# Sheet.net
KiCad netlist of a schematic drawn in Altium Designer
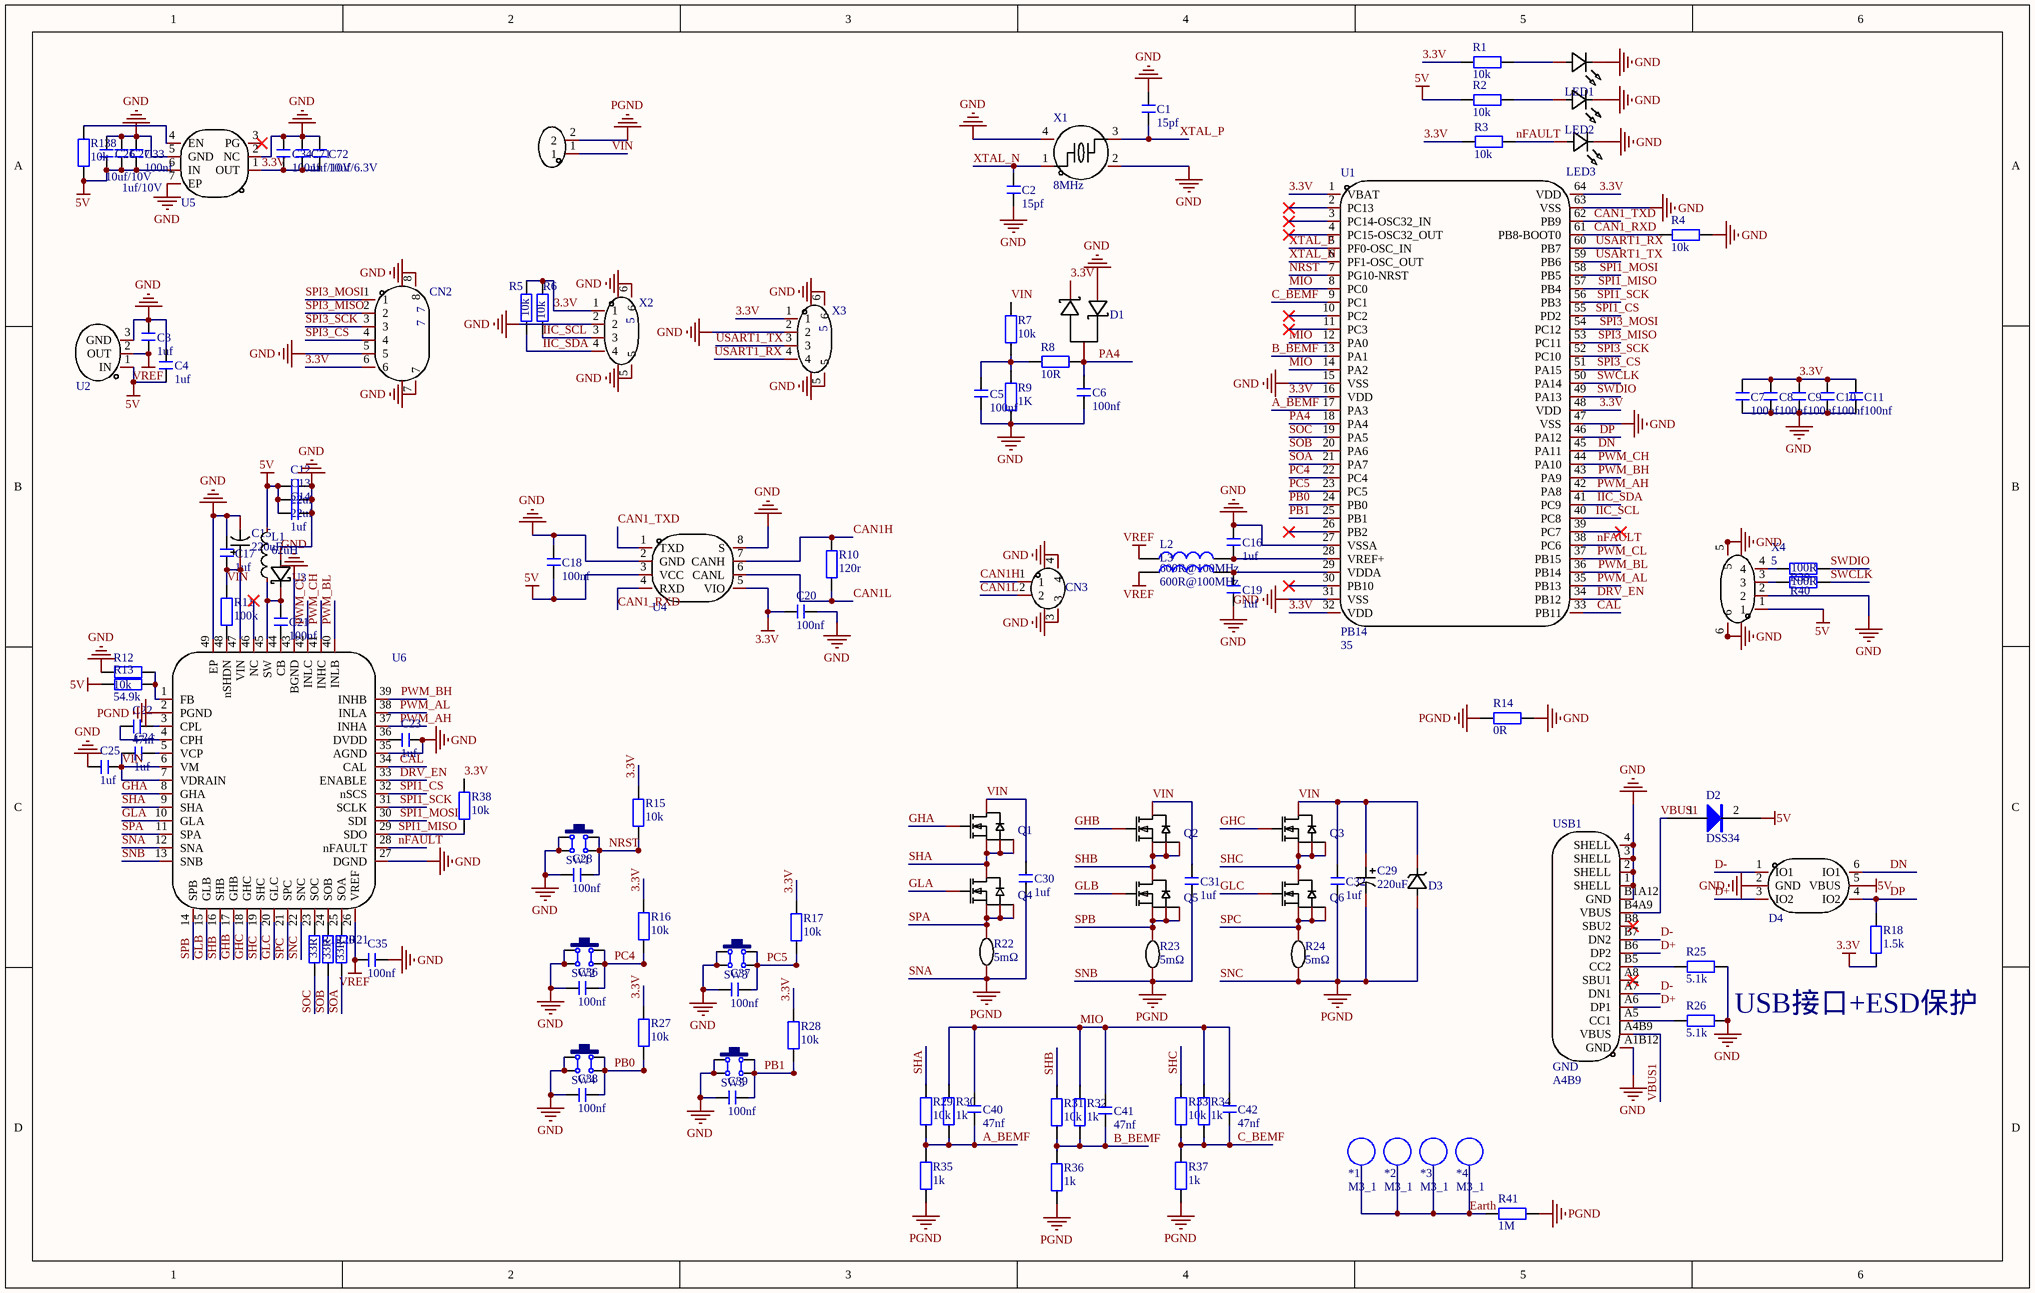
[diagram p0: Sheet.SchDoc]

(export (version "E")
  (design (tool "Eeschema 10.0.6"))
  (components
    (comp (ref "*1")
      (value "M3_1")
      (footprint "M3 125X250")
      (description "铜柱孔")
      (fields (field (name "版权归属") "源创客"))
      (libsource (lib "自用") (part "M3_1"))
    )
    (comp (ref "*2")
      (value "M3_1")
      (footprint "M3 125X250")
      (description "铜柱孔")
      (fields (field (name "版权归属") "源创客"))
      (libsource (lib "自用") (part "M3_1"))
    )
    (comp (ref "*3")
      (value "M3_1")
      (footprint "M3 125X250")
      (description "铜柱孔")
      (fields (field (name "版权归属") "源创客"))
      (libsource (lib "自用") (part "M3_1"))
    )
    (comp (ref "*4")
      (value "M3_1")
      (footprint "M3 125X250")
      (description "铜柱孔")
      (fields (field (name "版权归属") "源创客"))
      (libsource (lib "自用") (part "M3_1"))
    )
    (comp (ref "C1")
      (value "15pf")
      (footprint "C0402")
      (description "无极性电容")
      (fields (field (name "版权归属") "源创客"))
      (libsource (lib "自用") (part "C"))
    )
    (comp (ref "C2")
      (value "15pf")
      (footprint "C0402")
      (description "无极性电容")
      (fields (field (name "版权归属") "源创客"))
      (libsource (lib "自用") (part "C"))
    )
    (comp (ref "C3")
      (value "1uf")
      (footprint "C0402")
      (description "无极性电容")
      (fields (field (name "版权归属") "源创客"))
      (libsource (lib "自用") (part "C"))
    )
    (comp (ref "C4")
      (value "1uf")
      (footprint "C0402")
      (description "无极性电容")
      (fields (field (name "版权归属") "源创客"))
      (libsource (lib "自用") (part "C"))
    )
    (comp (ref "C5")
      (value "100nf")
      (footprint "C0402")
      (description "无极性电容")
      (fields (field (name "版权归属") "源创客"))
      (libsource (lib "自用") (part "C"))
    )
    (comp (ref "C6")
      (value "100nf")
      (footprint "C0402")
      (description "无极性电容")
      (fields (field (name "版权归属") "源创客"))
      (libsource (lib "自用") (part "C"))
    )
    (comp (ref "C7")
      (value "100nf")
      (footprint "C0402")
      (description "无极性电容")
      (fields (field (name "版权归属") "源创客"))
      (libsource (lib "自用") (part "C"))
    )
    (comp (ref "C8")
      (value "100nf")
      (footprint "C0402")
      (description "无极性电容")
      (fields (field (name "版权归属") "源创客"))
      (libsource (lib "自用") (part "C"))
    )
    (comp (ref "C9")
      (value "100nf")
      (footprint "C0402")
      (description "无极性电容")
      (fields (field (name "版权归属") "源创客"))
      (libsource (lib "自用") (part "C"))
    )
    (comp (ref "C10")
      (value "100nf")
      (footprint "C0402")
      (description "无极性电容")
      (fields (field (name "版权归属") "源创客"))
      (libsource (lib "自用") (part "C"))
    )
    (comp (ref "C11")
      (value "100nf")
      (footprint "C0402")
      (description "无极性电容")
      (fields (field (name "版权归属") "源创客"))
      (libsource (lib "自用") (part "C"))
    )
    (comp (ref "C12")
      (value "22uf")
      (footprint "C0402")
      (description "无极性电容")
      (fields (field (name "版权归属") "源创客"))
      (libsource (lib "自用") (part "C"))
    )
    (comp (ref "C13")
      (value "22uf")
      (footprint "C0402")
      (description "无极性电容")
      (fields (field (name "版权归属") "源创客"))
      (libsource (lib "自用") (part "C"))
    )
    (comp (ref "C14")
      (value "1uf")
      (footprint "C0402")
      (description "无极性电容")
      (fields (field (name "版权归属") "源创客"))
      (libsource (lib "自用") (part "C"))
    )
    (comp (ref "C15")
      (value "220uF")
      (footprint "CAP 2.5*5*11")
      (description "容值:220uF;精度:±20%;额定电压:50V;纹波电流:3.5A@100kHz;等效串联电阻(ESR):20mΩ@100kHz;类型:聚合物;")
      (fields (field (name "MANUFACTURER") "JIERR(捷而瑞)") (field (name "MANUFACTURER PART") "PA50V220M10x12"))
      (libsource (lib "自用") (part "电解电容M10*12"))
    )
    (comp (ref "C16")
      (value "1uf")
      (footprint "C0402")
      (description "无极性电容")
      (fields (field (name "版权归属") "源创客"))
      (libsource (lib "自用") (part "C"))
    )
    (comp (ref "C17")
      (value "1uf")
      (footprint "C1206")
      (description "无极性电容")
      (fields (field (name "版权归属") "源创客"))
      (libsource (lib "自用") (part "C"))
    )
    (comp (ref "C18")
      (value "100nf")
      (footprint "C0402")
      (description "无极性电容")
      (fields (field (name "版权归属") "源创客"))
      (libsource (lib "自用") (part "C"))
    )
    (comp (ref "C19")
      (value "1uf")
      (footprint "C0402")
      (description "无极性电容")
      (fields (field (name "版权归属") "源创客"))
      (libsource (lib "自用") (part "C"))
    )
    (comp (ref "C20")
      (value "100nf")
      (footprint "C0402")
      (description "无极性电容")
      (fields (field (name "版权归属") "源创客"))
      (libsource (lib "自用") (part "C"))
    )
    (comp (ref "C21")
      (value "100nf")
      (footprint "C0402")
      (description "无极性电容")
      (fields (field (name "版权归属") "源创客"))
      (libsource (lib "自用") (part "C"))
    )
    (comp (ref "C22")
      (value "47nf")
      (footprint "C0402")
      (description "无极性电容")
      (fields (field (name "版权归属") "源创客"))
      (libsource (lib "自用") (part "C"))
    )
    (comp (ref "C23")
      (value "1uf")
      (footprint "C0402")
      (description "无极性电容")
      (fields (field (name "版权归属") "源创客"))
      (libsource (lib "自用") (part "C"))
    )
    (comp (ref "C24")
      (value "1uf")
      (footprint "C0402")
      (description "无极性电容")
      (fields (field (name "版权归属") "源创客"))
      (libsource (lib "自用") (part "C"))
    )
    (comp (ref "C25")
      (value "1uf")
      (footprint "C0402")
      (description "无极性电容")
      (fields (field (name "版权归属") "源创客"))
      (libsource (lib "自用") (part "C"))
    )
    (comp (ref "C26")
      (value "10uf/10V")
      (footprint "C0603")
      (description "无极性电容")
      (fields (field (name "版权归属") "源创客"))
      (libsource (lib "自用") (part "C"))
    )
    (comp (ref "C27")
      (value "1uf/10V")
      (footprint "C0402")
      (description "无极性电容")
      (fields (field (name "版权归属") "源创客"))
      (libsource (lib "自用") (part "C"))
    )
    (comp (ref "C28")
      (value "100nf")
      (footprint "C0402")
      (description "无极性电容")
      (fields (field (name "版权归属") "源创客"))
      (libsource (lib "自用") (part "C"))
    )
    (comp (ref "C29")
      (value "220uF")
      (footprint "CAP-TH_BD10.0-P5.00-D0.6-FD_2")
      (description "容值:220uF;精度:±20%;额定电压:50V;纹波电流:3.5A@100kHz;等效串联电阻(ESR):20mΩ@100kHz;类型:聚合物;")
      (fields (field (name "MANUFACTURER") "JIERR(捷而瑞)") (field (name "MANUFACTURER PART") "PA50V220M10x12"))
      (libsource (lib "自用") (part "电解电容M10*12"))
    )
    (comp (ref "C30")
      (value "1uf")
      (footprint "C1206")
      (description "无极性电容")
      (fields (field (name "版权归属") "源创客"))
      (libsource (lib "自用") (part "C"))
    )
    (comp (ref "C31")
      (value "1uf")
      (footprint "C1206")
      (description "无极性电容")
      (fields (field (name "版权归属") "源创客"))
      (libsource (lib "自用") (part "C"))
    )
    (comp (ref "C32")
      (value "1uf")
      (footprint "C1206")
      (description "无极性电容")
      (fields (field (name "版权归属") "源创客"))
      (libsource (lib "自用") (part "C"))
    )
    (comp (ref "C33")
      (value "100nf")
      (footprint "C0402")
      (description "无极性电容")
      (fields (field (name "版权归属") "源创客"))
      (libsource (lib "自用") (part "C"))
    )
    (comp (ref "C34")
      (value "100nf")
      (footprint "C0402")
      (description "无极性电容")
      (fields (field (name "版权归属") "源创客"))
      (libsource (lib "自用") (part "C"))
    )
    (comp (ref "C35")
      (value "100nf")
      (footprint "C0402")
      (description "无极性电容")
      (fields (field (name "版权归属") "源创客"))
      (libsource (lib "自用") (part "C"))
    )
    (comp (ref "C36")
      (value "100nf")
      (footprint "C0402")
      (description "无极性电容")
      (fields (field (name "版权归属") "源创客"))
      (libsource (lib "自用") (part "C"))
    )
    (comp (ref "C37")
      (value "100nf")
      (footprint "C0402")
      (description "无极性电容")
      (fields (field (name "版权归属") "源创客"))
      (libsource (lib "自用") (part "C"))
    )
    (comp (ref "C38")
      (value "100nf")
      (footprint "C0402")
      (description "无极性电容")
      (fields (field (name "版权归属") "源创客"))
      (libsource (lib "自用") (part "C"))
    )
    (comp (ref "C39")
      (value "100nf")
      (footprint "C0402")
      (description "无极性电容")
      (fields (field (name "版权归属") "源创客"))
      (libsource (lib "自用") (part "C"))
    )
    (comp (ref "C40")
      (value "47nf")
      (footprint "C0402")
      (description "无极性电容")
      (fields (field (name "版权归属") "源创客"))
      (libsource (lib "自用") (part "C"))
    )
    (comp (ref "C41")
      (value "47nf")
      (footprint "C0402")
      (description "无极性电容")
      (fields (field (name "版权归属") "源创客"))
      (libsource (lib "自用") (part "C"))
    )
    (comp (ref "C42")
      (value "47nf")
      (footprint "C0402")
      (description "无极性电容")
      (fields (field (name "版权归属") "源创客"))
      (libsource (lib "自用") (part "C"))
    )
    (comp (ref "C71")
      (value "1uf/10V")
      (footprint "C0402")
      (description "无极性电容")
      (fields (field (name "版权归属") "源创客"))
      (libsource (lib "自用") (part "C"))
    )
    (comp (ref "C72")
      (value "10uf/6.3V")
      (footprint "C0603")
      (description "无极性电容")
      (fields (field (name "版权归属") "源创客"))
      (libsource (lib "自用") (part "C"))
    )
    (comp (ref "CN1")
      (value "XT30U-M")
      (footprint "CONN-TH_XT30U-M")
      (fields (field (name "MANUFACTURER") "AMASS(艾迈斯)"))
      (libsource (lib "自用") (part "XT30U-M"))
    )
    (comp (ref "CN2")
      (value "A1257WR-S-6P")
      (footprint "CONN-SMD_A1257WR-S-6P")
      (description "插针结构:1x6P;间距:1.25mm;安装方式:-;行距:-;总PIN数:6P;排数:1;每排PIN数:6;参考系列:GH;触头材质:黄铜;")
      (fields
        (field (name "MANUFACTURER") "CJT(长江连接器)")
        (field (name "NAME") "7")
        (field (name "NUMBER") "7")
      )
      (libsource (lib "自用") (part "GH1.25-6P"))
    )
    (comp (ref "CN3")
      (value "GH125-S02DCA-00")
      (footprint "GH1.25-2P-卧贴")
      (fields (field (name "MANUFACTURER") "JS(钜硕电子)"))
      (libsource (lib "自用") (part "GH125-2p"))
    )
    (comp (ref "D1")
      (value "LBAT54SLT1G")
      (footprint "SOT-23_L2.9-W1.3-P1.90-LS2.4-BR")
      (description "正向压降(Vf):400mV;直流反向耐压(Vr):30V;整流电流:200mA;")
      (fields (field (name "MANUFACTURER") "LRC(乐山无线电)"))
      (libsource (lib "自用") (part "LBAT54SLT1G"))
    )
    (comp (ref "D2")
      (value "DSS34")
      (footprint "SOD-123")
      (description "Diode 1N series")
      (libsource (lib "自用") (part "二极管"))
    )
    (comp (ref "D3")
      (value "SMBJ60A_C49066953")
      (footprint "SMB_L4.5-W3.7-LS5.4-RD")
      (description "极性:单向;反向截止电压(Vrwm):60V;钳位电压:96.8V;峰值脉冲电流(Ipp):6.2A;峰值脉冲功率(Ppp):600W;击穿电压:73.7V;")
      (fields (field (name "MANUFACTURER") "R+O(宏嘉诚)") (field (name "MANUFACTURER PART") "SMBJ60A"))
      (libsource (lib "自用") (part "SMBJ60A_C49066953"))
    )
    (comp (ref "D4")
      (value "USBLC6-2SC6_C2827654")
      (footprint "SOT-23-6_L2.9-W1.6-P0.95-LS2.8-BL")
      (description "极性:-;反向截止电压(Vrwm):-;最大钳位电压:-;峰值脉冲电流(Ipp)@10/1000us:-;峰值脉冲功率(Ppp)@10/1000us:-;击穿电压:-;")
      (fields
        (field (name "MANUFACTURER") "TECH PUBLIC(台舟)")
        (field (name "MANUFACTURER PART") "USBLC6-2SC6")
      )
      (libsource (lib "自用") (part "USBLC6-2SC6_C2827654"))
    )
    (comp (ref "L1")
      (value "62uH")
      (footprint "IND-SMD_L4.0-W4.0_FNR40XXS")
      (description "电感值:62uH;精度:±20%;额定电流:520mA;饱和电流(Isat):710mA;类型:磁胶屏蔽电感;")
      (fields (field (name "MANUFACTURER") "cjiang(长江微电)") (field (name "MANUFACTURER PART") "FNR4020S620MT"))
      (libsource (lib "自用") (part "FNR4020S620MT"))
    )
    (comp (ref "L2")
      (value "600R@100MHz")
      (footprint "L0603")
      (description "电感")
      (fields (field (name "版权归属") "源创客"))
      (libsource (lib "自用") (part "L_1"))
    )
    (comp (ref "L3")
      (value "600R@100MHz")
      (footprint "L0603")
      (description "电感")
      (fields (field (name "版权归属") "源创客"))
      (libsource (lib "自用") (part "L_1"))
    )
    (comp (ref "LED1")
      (value "XL-1005SURC")
      (footprint "LED0402-R-RD_RED")
      (description "发光颜色:红色;功率:55mW;正向电流:25mA;主波长:620nm;透镜颜色:无色透明透镜;色温:6000K~7000K;发光角度:120°;载带方式:正贴;工作温度:-30~+85;")
      (fields (field (name "MANUFACTURER") "XINGLIGHT(成兴光)"))
      (libsource (lib "自用") (part "LED_1"))
    )
    (comp (ref "LED2")
      (value "XL-1005SURC")
      (footprint "LED0402-R-RD_RED")
      (description "发光颜色:红色;功率:55mW;正向电流:25mA;主波长:620nm;透镜颜色:无色透明透镜;色温:6000K~7000K;发光角度:120°;载带方式:正贴;工作温度:-30~+85;")
      (fields (field (name "MANUFACTURER") "XINGLIGHT(成兴光)"))
      (libsource (lib "自用") (part "LED_1"))
    )
    (comp (ref "LED3")
      (value "XL-1005SURC")
      (footprint "LED0402-R-RD_RED")
      (description "发光颜色:红色;功率:55mW;正向电流:25mA;主波长:620nm;透镜颜色:无色透明透镜;色温:6000K~7000K;发光角度:120°;载带方式:正贴;工作温度:-30~+85;")
      (fields (field (name "MANUFACTURER") "XINGLIGHT(成兴光)"))
      (libsource (lib "自用") (part "LED_1"))
    )
    (comp (ref "Q1")
      (value "NCEP0160AG")
      (footprint "DFN-5_L4.9-W5.9-P1.27-LS6.2-BL")
      (fields (field (name "MANUFACTURER") "NCE(无锡新洁能)"))
      (libsource (lib "自用") (part "NCEP0160AG"))
    )
    (comp (ref "Q2")
      (value "NCEP0160AG")
      (footprint "DFN-5_L4.9-W5.9-P1.27-LS6.2-BL")
      (fields (field (name "MANUFACTURER") "NCE(无锡新洁能)"))
      (libsource (lib "自用") (part "NCEP0160AG"))
    )
    (comp (ref "Q3")
      (value "NCEP0160AG")
      (footprint "DFN-5_L4.9-W5.9-P1.27-LS6.2-BL")
      (fields (field (name "MANUFACTURER") "NCE(无锡新洁能)"))
      (libsource (lib "自用") (part "NCEP0160AG"))
    )
    (comp (ref "Q4")
      (value "NCEP0160AG")
      (footprint "DFN-5_L4.9-W5.9-P1.27-LS6.2-BL")
      (fields (field (name "MANUFACTURER") "NCE(无锡新洁能)"))
      (libsource (lib "自用") (part "NCEP0160AG"))
    )
    (comp (ref "Q5")
      (value "NCEP0160AG")
      (footprint "DFN-5_L4.9-W5.9-P1.27-LS6.2-BL")
      (fields (field (name "MANUFACTURER") "NCE(无锡新洁能)"))
      (libsource (lib "自用") (part "NCEP0160AG"))
    )
    (comp (ref "Q6")
      (value "NCEP0160AG")
      (footprint "DFN-5_L4.9-W5.9-P1.27-LS6.2-BL")
      (fields (field (name "MANUFACTURER") "NCE(无锡新洁能)"))
      (libsource (lib "自用") (part "NCEP0160AG"))
    )
    (comp (ref "R1")
      (value "10k")
      (footprint "R0402")
      (description "电阻")
      (fields (field (name "版权归属") "源创客"))
      (libsource (lib "自用") (part "R"))
    )
    (comp (ref "R2")
      (value "10k")
      (footprint "R0402")
      (description "电阻")
      (fields (field (name "版权归属") "源创客"))
      (libsource (lib "自用") (part "R"))
    )
    (comp (ref "R3")
      (value "10k")
      (footprint "R0402")
      (description "电阻")
      (fields (field (name "版权归属") "源创客"))
      (libsource (lib "自用") (part "R"))
    )
    (comp (ref "R4")
      (value "10k")
      (footprint "R0402")
      (description "电阻")
      (fields (field (name "版权归属") "源创客"))
      (libsource (lib "自用") (part "R"))
    )
    (comp (ref "R5")
      (value "10k")
      (footprint "R0402")
      (description "电阻")
      (fields (field (name "版权归属") "源创客"))
      (libsource (lib "自用") (part "R"))
    )
    (comp (ref "R6")
      (value "10k")
      (footprint "R0402")
      (description "电阻")
      (fields (field (name "版权归属") "源创客"))
      (libsource (lib "自用") (part "R"))
    )
    (comp (ref "R7")
      (value "10k")
      (footprint "R0402")
      (description "电阻")
      (fields (field (name "版权归属") "源创客"))
      (libsource (lib "自用") (part "R"))
    )
    (comp (ref "R8")
      (value "10R")
      (footprint "R0402")
      (description "电阻")
      (fields (field (name "版权归属") "源创客"))
      (libsource (lib "自用") (part "R"))
    )
    (comp (ref "R9")
      (value "1K")
      (footprint "R0402")
      (description "电阻")
      (fields (field (name "版权归属") "源创客"))
      (libsource (lib "自用") (part "R"))
    )
    (comp (ref "R10")
      (value "120r")
      (footprint "R0402")
      (description "电阻")
      (fields (field (name "版权归属") "源创客"))
      (libsource (lib "自用") (part "R"))
    )
    (comp (ref "R11")
      (value "100k")
      (footprint "R0402")
      (description "电阻")
      (fields (field (name "版权归属") "源创客"))
      (libsource (lib "自用") (part "R"))
    )
    (comp (ref "R12")
      (value "10k")
      (footprint "R0402")
      (description "电阻")
      (fields (field (name "版权归属") "源创客"))
      (libsource (lib "自用") (part "R"))
    )
    (comp (ref "R13")
      (value "54.9k")
      (footprint "R0402")
      (description "电阻")
      (fields (field (name "版权归属") "源创客"))
      (libsource (lib "自用") (part "R"))
    )
    (comp (ref "R14")
      (value "0R")
      (footprint "0805R")
      (description "电阻")
      (fields (field (name "版权归属") "源创客"))
      (libsource (lib "自用") (part "R"))
    )
    (comp (ref "R15")
      (value "10k")
      (footprint "R0402")
      (description "电阻")
      (fields (field (name "版权归属") "源创客"))
      (libsource (lib "自用") (part "R"))
    )
    (comp (ref "R16")
      (value "10k")
      (footprint "R0402")
      (description "电阻")
      (fields (field (name "版权归属") "源创客"))
      (libsource (lib "自用") (part "R"))
    )
    (comp (ref "R17")
      (value "10k")
      (footprint "R0402")
      (description "电阻")
      (fields (field (name "版权归属") "源创客"))
      (libsource (lib "自用") (part "R"))
    )
    (comp (ref "R18")
      (value "1.5k")
      (footprint "R0402")
      (description "电阻")
      (fields (field (name "版权归属") "源创客"))
      (libsource (lib "自用") (part "R"))
    )
    (comp (ref "R19")
      (value "33R")
      (footprint "R0402")
      (description "电阻")
      (fields (field (name "版权归属") "源创客"))
      (libsource (lib "自用") (part "R"))
    )
    (comp (ref "R20")
      (value "33R")
      (footprint "R0402")
      (description "电阻")
      (fields (field (name "版权归属") "源创客"))
      (libsource (lib "自用") (part "R"))
    )
    (comp (ref "R21")
      (value "33R")
      (footprint "R0402")
      (description "电阻")
      (fields (field (name "版权归属") "源创客"))
      (libsource (lib "自用") (part "R"))
    )
    (comp (ref "R22")
      (value "5mΩ")
      (footprint "R2512")
      (description "电阻类型:采样电阻;阻值:5mΩ;精度:±1%;功率:2W;安装方式:贴片;")
      (fields
        (field (name "MANUFACTURER") "Milliohm(毫欧)")
        (field (name "MANUFACTURER PART") "HoYLR2512-2W-5mR-1%")
      )
      (libsource (lib "自用") (part "HoYLR2512-2W-5mR-1%"))
    )
    (comp (ref "R23")
      (value "5mΩ")
      (footprint "R2512")
      (description "电阻类型:采样电阻;阻值:5mΩ;精度:±1%;功率:2W;安装方式:贴片;")
      (fields
        (field (name "MANUFACTURER") "Milliohm(毫欧)")
        (field (name "MANUFACTURER PART") "HoYLR2512-2W-5mR-1%")
      )
      (libsource (lib "自用") (part "HoYLR2512-2W-5mR-1%"))
    )
    (comp (ref "R24")
      (value "5mΩ")
      (footprint "R2512")
      (description "电阻类型:采样电阻;阻值:5mΩ;精度:±1%;功率:2W;安装方式:贴片;")
      (fields
        (field (name "MANUFACTURER") "Milliohm(毫欧)")
        (field (name "MANUFACTURER PART") "HoYLR2512-2W-5mR-1%")
      )
      (libsource (lib "自用") (part "HoYLR2512-2W-5mR-1%"))
    )
    (comp (ref "R25")
      (value "5.1k")
      (footprint "R0402")
      (description "电阻")
      (fields (field (name "版权归属") "源创客"))
      (libsource (lib "自用") (part "R"))
    )
    (comp (ref "R26")
      (value "5.1k")
      (footprint "R0402")
      (description "电阻")
      (fields (field (name "版权归属") "源创客"))
      (libsource (lib "自用") (part "R"))
    )
    (comp (ref "R27")
      (value "10k")
      (footprint "R0402")
      (description "电阻")
      (fields (field (name "版权归属") "源创客"))
      (libsource (lib "自用") (part "R"))
    )
    (comp (ref "R28")
      (value "10k")
      (footprint "R0402")
      (description "电阻")
      (fields (field (name "版权归属") "源创客"))
      (libsource (lib "自用") (part "R"))
    )
    (comp (ref "R29")
      (value "10k")
      (footprint "R0402")
      (description "电阻")
      (fields (field (name "版权归属") "源创客"))
      (libsource (lib "自用") (part "R"))
    )
    (comp (ref "R30")
      (value "1k")
      (footprint "R0402")
      (description "电阻")
      (fields (field (name "版权归属") "源创客"))
      (libsource (lib "自用") (part "R"))
    )
    (comp (ref "R31")
      (value "10k")
      (footprint "R0402")
      (description "电阻")
      (fields (field (name "版权归属") "源创客"))
      (libsource (lib "自用") (part "R"))
    )
    (comp (ref "R32")
      (value "1k")
      (footprint "R0402")
      (description "电阻")
      (fields (field (name "版权归属") "源创客"))
      (libsource (lib "自用") (part "R"))
    )
    (comp (ref "R33")
      (value "10k")
      (footprint "R0402")
      (description "电阻")
      (fields (field (name "版权归属") "源创客"))
      (libsource (lib "自用") (part "R"))
    )
    (comp (ref "R34")
      (value "1k")
      (footprint "R0402")
      (description "电阻")
      (fields (field (name "版权归属") "源创客"))
      (libsource (lib "自用") (part "R"))
    )
    (comp (ref "R35")
      (value "1k")
      (footprint "R0402")
      (description "电阻")
      (fields (field (name "版权归属") "源创客"))
      (libsource (lib "自用") (part "R"))
    )
    (comp (ref "R36")
      (value "1k")
      (footprint "R0402")
      (description "电阻")
      (fields (field (name "版权归属") "源创客"))
      (libsource (lib "自用") (part "R"))
    )
    (comp (ref "R37")
      (value "1k")
      (footprint "R0402")
      (description "电阻")
      (fields (field (name "版权归属") "源创客"))
      (libsource (lib "自用") (part "R"))
    )
    (comp (ref "R38")
      (value "10k")
      (footprint "R0402")
      (description "电阻")
      (fields (field (name "版权归属") "源创客"))
      (libsource (lib "自用") (part "R"))
    )
    (comp (ref "R39")
      (value "100R")
      (footprint "R0402")
      (description "电阻")
      (fields (field (name "版权归属") "源创客"))
      (libsource (lib "自用") (part "R"))
    )
    (comp (ref "R40")
      (value "100R")
      (footprint "R0402")
      (description "电阻")
      (fields (field (name "版权归属") "源创客"))
      (libsource (lib "自用") (part "R"))
    )
    (comp (ref "R41")
      (value "1M")
      (footprint "0805R")
      (description "电阻")
      (fields (field (name "版权归属") "源创客"))
      (libsource (lib "自用") (part "R"))
    )
    (comp (ref "R138")
      (value "10k")
      (footprint "R0402")
      (description "电阻")
      (fields (field (name "版权归属") "源创客"))
      (libsource (lib "自用") (part "R"))
    )
    (comp (ref "SW1")
      (value "smd-4*4*1.5")
      (footprint "TSW SMD-4*4*1.5")
      (description "轻触开关")
      (fields (field (name "版权归属") "源创客"))
      (libsource (lib "自用") (part "TSW DIP-6x6"))
    )
    (comp (ref "SW2")
      (value "smd-4*4*1.5")
      (footprint "TSW SMD-4*4*1.5")
      (description "轻触开关")
      (fields (field (name "版权归属") "源创客"))
      (libsource (lib "自用") (part "TSW DIP-6x6"))
    )
    (comp (ref "SW3")
      (value "smd-4*4*1.5")
      (footprint "TSW SMD-4*4*1.5")
      (description "轻触开关")
      (fields (field (name "版权归属") "源创客"))
      (libsource (lib "自用") (part "TSW DIP-6x6"))
    )
    (comp (ref "SW4")
      (value "smd-4*4*1.5")
      (footprint "TSW SMD-4*4*1.5")
      (description "轻触开关")
      (fields (field (name "版权归属") "源创客"))
      (libsource (lib "自用") (part "TSW DIP-6x6"))
    )
    (comp (ref "SW5")
      (value "smd-4*4*1.5")
      (footprint "TSW SMD-4*4*1.5")
      (description "轻触开关")
      (fields (field (name "版权归属") "源创客"))
      (libsource (lib "自用") (part "TSW DIP-6x6"))
    )
    (comp (ref "U1")
      (value "STM32G474RET6")
      (footprint "LQFP-64_L10.0-W10.0-P0.50-LS12.0-BL")
      (description "CPU内核:ARM-M4;CPU最大主频:170MHz;应用领域:-;")
      (fields
        (field (name "MANUFACTURER") "ST(意法半导体)")
        (field (name "NAME") "PB14")
        (field (name "NUMBER") "35")
      )
      (libsource (lib "自用") (part "STM32G474RET6"))
    )
    (comp (ref "U2")
      (value "REF3033AIDBZR")
      (footprint "SOT-23-3_L3.0-W1.7-P0.95-LS2.9-BR")
      (description "输出类型:固定;工作电压:3.35V~5.5V;输出电压:3.3V;输出电流:25mA;精度:±0.2%;")
      (fields (field (name "MANUFACTURER") "TI(德州仪器)") (field (name "TOLERANCE") "±0.2%"))
      (libsource (lib "自用") (part "REF3033AIDBZR"))
    )
    (comp (ref "U3")
      (value "DSK16_C22466351")
      (footprint "SOD-123FL_L2.8-W1.9-LS3.7-RD")
      (description "二极管配置:独立式;正向压降(Vf):700mV@1A;直流反向耐压(Vr):60V;整流电流:1A;")
      (fields (field (name "MANUFACTURER") "R+O(宏嘉诚)") (field (name "MANUFACTURER PART") "DSK16"))
      (libsource (lib "自用") (part "DSK16_C22466351"))
    )
    (comp (ref "U4")
      (value "TJA1051T/3")
      (footprint "SOP-8_L4.9-W3.9-P1.27-LS6.0-BL-1")
      (fields (field (name "MANUFACTURER") "Tokmas(托克马斯)"))
      (libsource (lib "自用") (part "TJA1051T/3"))
    )
    (comp (ref "U5")
      (value "LP5912-3.3DRVR")
      (footprint "WSON-6_L2.0-W2.0-P0.65-TL-EP")
      (description "输出类型:固定;最大输入电压:6.5V;输出电压:3.3V;输出电流:500mA;输出极性:正极;")
      (fields (field (name "MANUFACTURER") "TI(德州仪器)"))
      (libsource (lib "自用") (part "LP5912-3.3DRVR"))
    )
    (comp (ref "U6")
      (value "DRV8323RSRGZT")
      (footprint "VQFN-48_L7.0-W7.0-P0.50-BL-EP5.5")
      (description "DRV8323R 具有降压稳压器和电流分流放大器的最大 65V 三相智能栅极驱动器")
      (fields (field (name "MANUFACTURER") "TI(德州仪器)"))
      (libsource (lib "自用") (part "DRV8323RSRGZT"))
    )
    (comp (ref "USB1")
      (value "TYPE-C16PIN")
      (footprint "USB-C-SMD_TYPE-C16PIN")
      (description "连接器类型:Type-C;标准:-;公母:母;端口数量:1;触点数量:16P;安装方式:卧贴;额定电流 - 电源:3A;工作温度范围:-40~+85;")
      (fields
        (field (name "MANUFACTURER") "SHOU HAN(首韩)")
        (field (name "NAME") "GND")
        (field (name "NUMBER") "A4B9")
      )
      (libsource (lib "自用") (part "TYPE-C16PIN"))
    )
    (comp (ref "X1")
      (value "8MHz")
      (footprint "CRYSTAL-SMD_4P-L3.2-W2.5-BL")
      (description "频率:16MHz;负载电容:12pF;频率公差:±10ppm;")
      (fields
        (field (name "MANUFACTURER") "YXC(扬兴晶振)")
        (field (name "MANUFACTURER PART") "XL2EL89CSI-111YLC-25M")
      )
      (libsource (lib "自用") (part "XL2EL89CSI-111YLC-25M"))
    )
    (comp (ref "X2")
      (value "GH125-S04CCA-00")
      (footprint "GH1.25-4P-卧贴")
      (description "插针结构:1x4P;间距:1.25mm;安装方式:立贴;行距:-;总PIN数:4P;排数:1;每排PIN数:4;参考系列:-;额定电流:1A;工作温度范围:-25~+85;")
      (fields (field (name "MANUFACTURER") "JS(钜硕电子)") (field (name "NUMBER") "5"))
      (libsource (lib "自用") (part "GH1.25-4P_1"))
    )
    (comp (ref "X3")
      (value "GH125-S04CCA-00")
      (footprint "GH1.25-4P-卧贴")
      (description "插针结构:1x4P;间距:1.25mm;安装方式:立贴;行距:-;总PIN数:4P;排数:1;每排PIN数:4;参考系列:-;额定电流:1A;工作温度范围:-25~+85;")
      (fields (field (name "MANUFACTURER") "JS(钜硕电子)") (field (name "NUMBER") "5"))
      (libsource (lib "自用") (part "GH1.25-4P_1"))
    )
    (comp (ref "X4")
      (value "GH125-S04CCA-00")
      (footprint "GH1.25-4P-卧贴")
      (description "插针结构:1x4P;间距:1.25mm;安装方式:立贴;行距:-;总PIN数:4P;排数:1;每排PIN数:4;参考系列:-;额定电流:1A;工作温度范围:-25~+85;")
      (fields (field (name "MANUFACTURER") "JS(钜硕电子)") (field (name "NUMBER") "5"))
      (libsource (lib "自用") (part "GH1.25-4P_1"))
    )
  )
  (nets
    (net (code "1") (name "/A_BEMF") (class "Default")
      (node (ref "C40") (pin "1") (pinfunction "1_1") (pintype "passive"))
      (node (ref "R29") (pin "1") (pinfunction "1_1") (pintype "passive"))
      (node (ref "R30") (pin "1") (pinfunction "1_1") (pintype "passive"))
      (node (ref "R35") (pin "2") (pinfunction "2_2") (pintype "passive"))
      (node (ref "U1") (pin "17") (pinfunction "PA3_17") (pintype "passive"))
    )
    (net (code "2") (name "/B_BEMF") (class "Default")
      (node (ref "C41") (pin "1") (pinfunction "1_1") (pintype "passive"))
      (node (ref "R31") (pin "1") (pinfunction "1_1") (pintype "passive"))
      (node (ref "R32") (pin "1") (pinfunction "1_1") (pintype "passive"))
      (node (ref "R36") (pin "2") (pinfunction "2_2") (pintype "passive"))
      (node (ref "U1") (pin "13") (pinfunction "PA1_13") (pintype "passive"))
    )
    (net (code "3") (name "/CAL") (class "Default")
      (node (ref "U1") (pin "33") (pinfunction "PB11_33") (pintype "passive"))
      (node (ref "U6") (pin "34") (pinfunction "CAL_34") (pintype "passive"))
    )
    (net (code "4") (name "/CAN1H") (class "Default")
      (node (ref "CN3") (pin "1") (pinfunction "1_1") (pintype "passive"))
      (node (ref "R10") (pin "2") (pinfunction "2_2") (pintype "passive"))
      (node (ref "U4") (pin "7") (pinfunction "CANH_7") (pintype "passive"))
    )
    (net (code "5") (name "/CAN1L") (class "Default")
      (node (ref "CN3") (pin "2") (pinfunction "2_2") (pintype "passive"))
      (node (ref "R10") (pin "1") (pinfunction "1_1") (pintype "passive"))
      (node (ref "U4") (pin "6") (pinfunction "CANL_6") (pintype "passive"))
    )
    (net (code "6") (name "/CAN1_RXD") (class "Default")
      (node (ref "R4") (pin "2") (pinfunction "2_2") (pintype "passive"))
      (node (ref "U1") (pin "61") (pinfunction "PB8-BOOT0_61") (pintype "passive"))
      (node (ref "U4") (pin "4") (pinfunction "RXD_4") (pintype "passive"))
    )
    (net (code "7") (name "/CAN1_TXD") (class "Default")
      (node (ref "U1") (pin "62") (pinfunction "PB9_62") (pintype "passive"))
      (node (ref "U4") (pin "1") (pinfunction "TXD_1") (pintype "passive"))
    )
    (net (code "8") (name "/C_BEMF") (class "Default")
      (node (ref "C42") (pin "1") (pinfunction "1_1") (pintype "passive"))
      (node (ref "R33") (pin "1") (pinfunction "1_1") (pintype "passive"))
      (node (ref "R34") (pin "1") (pinfunction "1_1") (pintype "passive"))
      (node (ref "R37") (pin "2") (pinfunction "2_2") (pintype "passive"))
      (node (ref "U1") (pin "9") (pinfunction "PC1_9") (pintype "passive"))
    )
    (net (code "9") (name "/D+") (class "Default")
      (node (ref "D4") (pin "3") (pinfunction "IO2_3") (pintype "passive"))
      (node (ref "USB1") (pin "A6") (pinfunction "DP1_A6") (pintype "passive"))
      (node (ref "USB1") (pin "B6") (pinfunction "DP2_B6") (pintype "passive"))
    )
    (net (code "10") (name "/D-") (class "Default")
      (node (ref "D4") (pin "1") (pinfunction "IO1_1") (pintype "passive"))
      (node (ref "USB1") (pin "A7") (pinfunction "DN1_A7") (pintype "passive"))
      (node (ref "USB1") (pin "B7") (pinfunction "DN2_B7") (pintype "passive"))
    )
    (net (code "11") (name "/DN") (class "Default")
      (node (ref "D4") (pin "6") (pinfunction "IO1_6") (pintype "passive"))
      (node (ref "U1") (pin "45") (pinfunction "PA11_45") (pintype "passive"))
    )
    (net (code "12") (name "/DP") (class "Default")
      (node (ref "D4") (pin "4") (pinfunction "IO2_4") (pintype "passive"))
      (node (ref "R18") (pin "1") (pinfunction "1_1") (pintype "passive"))
      (node (ref "U1") (pin "46") (pinfunction "PA12_46") (pintype "passive"))
    )
    (net (code "13") (name "/DRV_EN") (class "Default")
      (node (ref "U1") (pin "34") (pinfunction "PB12_34") (pintype "passive"))
      (node (ref "U6") (pin "33") (pinfunction "ENABLE_33") (pintype "passive"))
    )
    (net (code "14") (name "/Earth") (class "Default")
      (node (ref "*1") (pin "1") (pinfunction "1_1") (pintype "passive"))
      (node (ref "*2") (pin "1") (pinfunction "1_1") (pintype "passive"))
      (node (ref "*3") (pin "1") (pinfunction "1_1") (pintype "passive"))
      (node (ref "*4") (pin "1") (pinfunction "1_1") (pintype "passive"))
      (node (ref "R41") (pin "2") (pinfunction "2_2") (pintype "passive"))
    )
    (net (code "15") (name "/GHA") (class "Default")
      (node (ref "Q1") (pin "4") (pinfunction "G_4") (pintype "passive"))
      (node (ref "U6") (pin "8") (pinfunction "GHA_8") (pintype "passive"))
    )
    (net (code "16") (name "/GHB") (class "Default")
      (node (ref "Q2") (pin "4") (pinfunction "G_4") (pintype "passive"))
      (node (ref "U6") (pin "17") (pinfunction "GHB_17") (pintype "passive"))
    )
    (net (code "17") (name "/GHC") (class "Default")
      (node (ref "Q3") (pin "4") (pinfunction "G_4") (pintype "passive"))
      (node (ref "U6") (pin "18") (pinfunction "GHC_18") (pintype "passive"))
    )
    (net (code "18") (name "/GLA") (class "Default")
      (node (ref "Q4") (pin "4") (pinfunction "G_4") (pintype "passive"))
      (node (ref "U6") (pin "10") (pinfunction "GLA_10") (pintype "passive"))
    )
    (net (code "19") (name "/GLB") (class "Default")
      (node (ref "Q5") (pin "4") (pinfunction "G_4") (pintype "passive"))
      (node (ref "U6") (pin "15") (pinfunction "GLB_15") (pintype "passive"))
    )
    (net (code "20") (name "/GLC") (class "Default")
      (node (ref "Q6") (pin "4") (pinfunction "G_4") (pintype "passive"))
      (node (ref "U6") (pin "20") (pinfunction "GLC_20") (pintype "passive"))
    )
    (net (code "21") (name "/IIC_SCL") (class "Default")
      (node (ref "R6") (pin "1") (pinfunction "1_1") (pintype "passive"))
      (node (ref "U1") (pin "40") (pinfunction "PC8_40") (pintype "passive"))
      (node (ref "X2") (pin "3") (pinfunction "3_3") (pintype "passive"))
    )
    (net (code "22") (name "/IIC_SDA") (class "Default")
      (node (ref "R5") (pin "1") (pinfunction "1_1") (pintype "passive"))
      (node (ref "U1") (pin "41") (pinfunction "PC9_41") (pintype "passive"))
      (node (ref "X2") (pin "4") (pinfunction "4_4") (pintype "passive"))
    )
    (net (code "23") (name "/MIO") (class "Default")
      (node (ref "C40") (pin "2") (pinfunction "2_2") (pintype "passive"))
      (node (ref "C41") (pin "2") (pinfunction "2_2") (pintype "passive"))
      (node (ref "C42") (pin "2") (pinfunction "2_2") (pintype "passive"))
      (node (ref "R30") (pin "2") (pinfunction "2_2") (pintype "passive"))
      (node (ref "R32") (pin "2") (pinfunction "2_2") (pintype "passive"))
      (node (ref "R34") (pin "2") (pinfunction "2_2") (pintype "passive"))
      (node (ref "U1") (pin "12") (pinfunction "PA0_12") (pintype "passive"))
      (node (ref "U1") (pin "14") (pinfunction "PA2_14") (pintype "passive"))
      (node (ref "U1") (pin "8") (pinfunction "PC0_8") (pintype "passive"))
    )
    (net (code "24") (name "/NRST") (class "Default")
      (node (ref "C28") (pin "2") (pinfunction "2_2") (pintype "passive"))
      (node (ref "R15") (pin "1") (pinfunction "1_1") (pintype "passive"))
      (node (ref "SW1") (pin "2") (pinfunction "2_2") (pintype "passive"))
      (node (ref "SW1") (pin "3") (pinfunction "3_3") (pintype "passive"))
      (node (ref "U1") (pin "7") (pinfunction "PG10-NRST_7") (pintype "passive"))
    )
    (net (code "25") (name "/PA4") (class "Default")
      (node (ref "C6") (pin "1") (pinfunction "1_1") (pintype "passive"))
      (node (ref "D1") (pin "3") (pinfunction "AK_3") (pintype "passive"))
      (node (ref "R8") (pin "1") (pinfunction "1_1") (pintype "passive"))
      (node (ref "U1") (pin "18") (pinfunction "PA4_18") (pintype "passive"))
    )
    (net (code "26") (name "/PB0") (class "Default")
      (node (ref "C38") (pin "2") (pinfunction "2_2") (pintype "passive"))
      (node (ref "R27") (pin "1") (pinfunction "1_1") (pintype "passive"))
      (node (ref "SW4") (pin "2") (pinfunction "2_2") (pintype "passive"))
      (node (ref "SW4") (pin "3") (pinfunction "3_3") (pintype "passive"))
      (node (ref "U1") (pin "24") (pinfunction "PB0_24") (pintype "passive"))
    )
    (net (code "27") (name "/PB1") (class "Default")
      (node (ref "C39") (pin "2") (pinfunction "2_2") (pintype "passive"))
      (node (ref "R28") (pin "1") (pinfunction "1_1") (pintype "passive"))
      (node (ref "SW5") (pin "2") (pinfunction "2_2") (pintype "passive"))
      (node (ref "SW5") (pin "3") (pinfunction "3_3") (pintype "passive"))
      (node (ref "U1") (pin "25") (pinfunction "PB1_25") (pintype "passive"))
    )
    (net (code "28") (name "/PC4") (class "Default")
      (node (ref "C36") (pin "2") (pinfunction "2_2") (pintype "passive"))
      (node (ref "R16") (pin "1") (pinfunction "1_1") (pintype "passive"))
      (node (ref "SW2") (pin "2") (pinfunction "2_2") (pintype "passive"))
      (node (ref "SW2") (pin "3") (pinfunction "3_3") (pintype "passive"))
      (node (ref "U1") (pin "22") (pinfunction "PC4_22") (pintype "passive"))
    )
    (net (code "29") (name "/PC5") (class "Default")
      (node (ref "C37") (pin "2") (pinfunction "2_2") (pintype "passive"))
      (node (ref "R17") (pin "1") (pinfunction "1_1") (pintype "passive"))
      (node (ref "SW3") (pin "2") (pinfunction "2_2") (pintype "passive"))
      (node (ref "SW3") (pin "3") (pinfunction "3_3") (pintype "passive"))
      (node (ref "U1") (pin "23") (pinfunction "PC5_23") (pintype "passive"))
    )
    (net (code "30") (name "/PWM_AH") (class "Default")
      (node (ref "U1") (pin "42") (pinfunction "PA8_42") (pintype "passive"))
      (node (ref "U6") (pin "37") (pinfunction "INHA_37") (pintype "passive"))
    )
    (net (code "31") (name "/PWM_AL") (class "Default")
      (node (ref "U1") (pin "35") (pinfunction "PB13_35") (pintype "passive"))
      (node (ref "U6") (pin "38") (pinfunction "INLA_38") (pintype "passive"))
    )
    (net (code "32") (name "/PWM_BH") (class "Default")
      (node (ref "U1") (pin "43") (pinfunction "PA9_43") (pintype "passive"))
      (node (ref "U6") (pin "39") (pinfunction "INHB_39") (pintype "passive"))
    )
    (net (code "33") (name "/PWM_BL") (class "Default")
      (node (ref "U1") (pin "36") (pinfunction "PB14_36") (pintype "passive"))
      (node (ref "U6") (pin "40") (pinfunction "INLB_40") (pintype "passive"))
    )
    (net (code "34") (name "/PWM_CH") (class "Default")
      (node (ref "U1") (pin "44") (pinfunction "PA10_44") (pintype "passive"))
      (node (ref "U6") (pin "41") (pinfunction "INHC_41") (pintype "passive"))
    )
    (net (code "35") (name "/PWM_CL") (class "Default")
      (node (ref "U1") (pin "37") (pinfunction "PB15_37") (pintype "passive"))
      (node (ref "U6") (pin "42") (pinfunction "INLC_42") (pintype "passive"))
    )
    (net (code "36") (name "/SHA") (class "Default")
      (node (ref "Q1") (pin "1") (pinfunction "S_1") (pintype "passive"))
      (node (ref "Q1") (pin "2") (pinfunction "S_2") (pintype "passive"))
      (node (ref "Q1") (pin "3") (pinfunction "S_3") (pintype "passive"))
      (node (ref "Q4") (pin "5") (pinfunction "D_5") (pintype "passive"))
      (node (ref "R29") (pin "2") (pinfunction "2_2") (pintype "passive"))
      (node (ref "U6") (pin "9") (pinfunction "SHA_9") (pintype "passive"))
    )
    (net (code "37") (name "/SHB") (class "Default")
      (node (ref "Q2") (pin "1") (pinfunction "S_1") (pintype "passive"))
      (node (ref "Q2") (pin "2") (pinfunction "S_2") (pintype "passive"))
      (node (ref "Q2") (pin "3") (pinfunction "S_3") (pintype "passive"))
      (node (ref "Q5") (pin "5") (pinfunction "D_5") (pintype "passive"))
      (node (ref "R31") (pin "2") (pinfunction "2_2") (pintype "passive"))
      (node (ref "U6") (pin "16") (pinfunction "SHB_16") (pintype "passive"))
    )
    (net (code "38") (name "/SHC") (class "Default")
      (node (ref "Q3") (pin "1") (pinfunction "S_1") (pintype "passive"))
      (node (ref "Q3") (pin "2") (pinfunction "S_2") (pintype "passive"))
      (node (ref "Q3") (pin "3") (pinfunction "S_3") (pintype "passive"))
      (node (ref "Q6") (pin "5") (pinfunction "D_5") (pintype "passive"))
      (node (ref "R33") (pin "2") (pinfunction "2_2") (pintype "passive"))
      (node (ref "U6") (pin "19") (pinfunction "SHC_19") (pintype "passive"))
    )
    (net (code "39") (name "/SOA") (class "Default")
      (node (ref "R21") (pin "1") (pinfunction "1_1") (pintype "passive"))
      (node (ref "U1") (pin "21") (pinfunction "PA7_21") (pintype "passive"))
    )
    (net (code "40") (name "/SOB") (class "Default")
      (node (ref "R20") (pin "1") (pinfunction "1_1") (pintype "passive"))
      (node (ref "U1") (pin "20") (pinfunction "PA6_20") (pintype "passive"))
    )
    (net (code "41") (name "/SOC") (class "Default")
      (node (ref "R19") (pin "1") (pinfunction "1_1") (pintype "passive"))
      (node (ref "U1") (pin "19") (pinfunction "PA5_19") (pintype "passive"))
    )
    (net (code "42") (name "/SPA") (class "Default")
      (node (ref "Q4") (pin "1") (pinfunction "S_1") (pintype "passive"))
      (node (ref "Q4") (pin "2") (pinfunction "S_2") (pintype "passive"))
      (node (ref "Q4") (pin "3") (pinfunction "S_3") (pintype "passive"))
      (node (ref "R22") (pin "2") (pinfunction "2_2") (pintype "passive"))
      (node (ref "U6") (pin "11") (pinfunction "SPA_11") (pintype "passive"))
    )
    (net (code "43") (name "/SPB") (class "Default")
      (node (ref "Q5") (pin "1") (pinfunction "S_1") (pintype "passive"))
      (node (ref "Q5") (pin "2") (pinfunction "S_2") (pintype "passive"))
      (node (ref "Q5") (pin "3") (pinfunction "S_3") (pintype "passive"))
      (node (ref "R23") (pin "2") (pinfunction "2_2") (pintype "passive"))
      (node (ref "U6") (pin "14") (pinfunction "SPB_14") (pintype "passive"))
    )
    (net (code "44") (name "/SPC") (class "Default")
      (node (ref "Q6") (pin "1") (pinfunction "S_1") (pintype "passive"))
      (node (ref "Q6") (pin "2") (pinfunction "S_2") (pintype "passive"))
      (node (ref "Q6") (pin "3") (pinfunction "S_3") (pintype "passive"))
      (node (ref "R24") (pin "2") (pinfunction "2_2") (pintype "passive"))
      (node (ref "U6") (pin "21") (pinfunction "SPC_21") (pintype "passive"))
    )
    (net (code "45") (name "/SPI1_CS") (class "Default")
      (node (ref "U1") (pin "55") (pinfunction "PD2_55") (pintype "passive"))
      (node (ref "U6") (pin "32") (pinfunction "nSCS_32") (pintype "passive"))
    )
    (net (code "46") (name "/SPI1_MISO") (class "Default")
      (node (ref "R38") (pin "1") (pinfunction "1_1") (pintype "passive"))
      (node (ref "U1") (pin "57") (pinfunction "PB4_57") (pintype "passive"))
      (node (ref "U6") (pin "29") (pinfunction "SDO_29") (pintype "passive"))
    )
    (net (code "47") (name "/SPI1_MOSI") (class "Default")
      (node (ref "U1") (pin "58") (pinfunction "PB5_58") (pintype "passive"))
      (node (ref "U6") (pin "30") (pinfunction "SDI_30") (pintype "passive"))
    )
    (net (code "48") (name "/SPI1_SCK") (class "Default")
      (node (ref "U1") (pin "56") (pinfunction "PB3_56") (pintype "passive"))
      (node (ref "U6") (pin "31") (pinfunction "SCLK_31") (pintype "passive"))
    )
    (net (code "49") (name "/SPI3_CS") (class "Default")
      (node (ref "CN2") (pin "4") (pinfunction "4_4") (pintype "passive"))
      (node (ref "U1") (pin "51") (pinfunction "PA15_51") (pintype "passive"))
    )
    (net (code "50") (name "/SPI3_MISO") (class "Default")
      (node (ref "CN2") (pin "2") (pinfunction "2_2") (pintype "passive"))
      (node (ref "U1") (pin "53") (pinfunction "PC11_53") (pintype "passive"))
    )
    (net (code "51") (name "/SPI3_MOSI") (class "Default")
      (node (ref "CN2") (pin "1") (pinfunction "1_1") (pintype "passive"))
      (node (ref "U1") (pin "54") (pinfunction "PC12_54") (pintype "passive"))
    )
    (net (code "52") (name "/SPI3_SCK") (class "Default")
      (node (ref "CN2") (pin "3") (pinfunction "3_3") (pintype "passive"))
      (node (ref "U1") (pin "52") (pinfunction "PC10_52") (pintype "passive"))
    )
    (net (code "53") (name "/SWCLK") (class "Default")
      (node (ref "R40") (pin "2") (pinfunction "2_2") (pintype "passive"))
      (node (ref "U1") (pin "50") (pinfunction "PA14_50") (pintype "passive"))
    )
    (net (code "54") (name "/SWDIO") (class "Default")
      (node (ref "R39") (pin "2") (pinfunction "2_2") (pintype "passive"))
      (node (ref "U1") (pin "49") (pinfunction "PA13_49") (pintype "passive"))
    )
    (net (code "55") (name "/USART1_RX") (class "Default")
      (node (ref "U1") (pin "60") (pinfunction "PB7_60") (pintype "passive"))
      (node (ref "X3") (pin "4") (pinfunction "4_4") (pintype "passive"))
    )
    (net (code "56") (name "/USART1_TX") (class "Default")
      (node (ref "U1") (pin "59") (pinfunction "PB6_59") (pintype "passive"))
      (node (ref "X3") (pin "3") (pinfunction "3_3") (pintype "passive"))
    )
    (net (code "57") (name "/VBUS1") (class "Default")
      (node (ref "D2") (pin "1") (pinfunction "1_1") (pintype "passive"))
      (node (ref "USB1") (pin "A4B9") (pinfunction "VBUS_A4B9") (pintype "passive"))
      (node (ref "USB1") (pin "B4A9") (pinfunction "VBUS_B4A9") (pintype "passive"))
    )
    (net (code "58") (name "/VIN") (class "Default")
      (node (ref "C15") (pin "1") (pinfunction "1_1") (pintype "passive"))
      (node (ref "C17") (pin "1") (pinfunction "1_1") (pintype "passive"))
      (node (ref "C24") (pin "1") (pinfunction "1_1") (pintype "passive"))
      (node (ref "C25") (pin "2") (pinfunction "2_2") (pintype "passive"))
      (node (ref "C29") (pin "1") (pinfunction "1_1") (pintype "passive"))
      (node (ref "C30") (pin "2") (pinfunction "2_2") (pintype "passive"))
      (node (ref "C31") (pin "2") (pinfunction "2_2") (pintype "passive"))
      (node (ref "C32") (pin "2") (pinfunction "2_2") (pintype "passive"))
      (node (ref "CN1") (pin "1") (pinfunction "1_1") (pintype "passive"))
      (node (ref "D3") (pin "1") (pinfunction "K_1") (pintype "passive"))
      (node (ref "Q1") (pin "5") (pinfunction "D_5") (pintype "passive"))
      (node (ref "Q2") (pin "5") (pinfunction "D_5") (pintype "passive"))
      (node (ref "Q3") (pin "5") (pinfunction "D_5") (pintype "passive"))
      (node (ref "R11") (pin "2") (pinfunction "2_2") (pintype "passive"))
      (node (ref "R7") (pin "2") (pinfunction "2_2") (pintype "passive"))
      (node (ref "U6") (pin "47") (pinfunction "VIN_47") (pintype "passive"))
      (node (ref "U6") (pin "6") (pinfunction "VM_6") (pintype "passive"))
      (node (ref "U6") (pin "7") (pinfunction "VDRAIN_7") (pintype "passive"))
    )
    (net (code "59") (name "/XTAL_N") (class "Default")
      (node (ref "C2") (pin "1") (pinfunction "1_1") (pintype "passive"))
      (node (ref "U1") (pin "6") (pinfunction "PF1-OSC_OUT_6") (pintype "passive"))
      (node (ref "X1") (pin "1") (pinfunction "1_1") (pintype "passive"))
    )
    (net (code "60") (name "/XTAL_P") (class "Default")
      (node (ref "C1") (pin "2") (pinfunction "2_2") (pintype "passive"))
      (node (ref "U1") (pin "5") (pinfunction "PF0-OSC_IN_5") (pintype "passive"))
      (node (ref "X1") (pin "3") (pinfunction "3_3") (pintype "passive"))
    )
    (net (code "61") (name "/nFAULT") (class "Default")
      (node (ref "LED3") (pin "1") (pinfunction "K_1") (pintype "passive"))
      (node (ref "R3") (pin "1") (pinfunction "1_1") (pintype "passive"))
      (node (ref "U1") (pin "38") (pinfunction "PC6_38") (pintype "passive"))
      (node (ref "U6") (pin "28") (pinfunction "nFAULT_28") (pintype "passive"))
    )
    (net (code "62") (name "3.3V") (class "Default")
      (node (ref "C10") (pin "1") (pinfunction "1_1") (pintype "passive"))
      (node (ref "C11") (pin "1") (pinfunction "1_1") (pintype "passive"))
      (node (ref "C20") (pin "2") (pinfunction "2_2") (pintype "passive"))
      (node (ref "C34") (pin "2") (pinfunction "2_2") (pintype "passive"))
      (node (ref "C7") (pin "1") (pinfunction "1_1") (pintype "passive"))
      (node (ref "C71") (pin "2") (pinfunction "2_2") (pintype "passive"))
      (node (ref "C72") (pin "2") (pinfunction "2_2") (pintype "passive"))
      (node (ref "C8") (pin "1") (pinfunction "1_1") (pintype "passive"))
      (node (ref "C9") (pin "1") (pinfunction "1_1") (pintype "passive"))
      (node (ref "CN2") (pin "6") (pinfunction "6_6") (pintype "passive"))
      (node (ref "D1") (pin "2") (pinfunction "K_2") (pintype "passive"))
      (node (ref "R1") (pin "2") (pinfunction "2_2") (pintype "passive"))
      (node (ref "R15") (pin "2") (pinfunction "2_2") (pintype "passive"))
      (node (ref "R16") (pin "2") (pinfunction "2_2") (pintype "passive"))
      (node (ref "R17") (pin "2") (pinfunction "2_2") (pintype "passive"))
      (node (ref "R18") (pin "2") (pinfunction "2_2") (pintype "passive"))
      (node (ref "R27") (pin "2") (pinfunction "2_2") (pintype "passive"))
      (node (ref "R28") (pin "2") (pinfunction "2_2") (pintype "passive"))
      (node (ref "R3") (pin "2") (pinfunction "2_2") (pintype "passive"))
      (node (ref "R38") (pin "2") (pinfunction "2_2") (pintype "passive"))
      (node (ref "R5") (pin "2") (pinfunction "2_2") (pintype "passive"))
      (node (ref "R6") (pin "2") (pinfunction "2_2") (pintype "passive"))
      (node (ref "U1") (pin "1") (pinfunction "VBAT_1") (pintype "passive"))
      (node (ref "U1") (pin "16") (pinfunction "VDD_16") (pintype "passive"))
      (node (ref "U1") (pin "32") (pinfunction "VDD_32") (pintype "passive"))
      (node (ref "U1") (pin "48") (pinfunction "VDD_48") (pintype "passive"))
      (node (ref "U1") (pin "64") (pinfunction "VDD_64") (pintype "passive"))
      (node (ref "U4") (pin "5") (pinfunction "VIO_5") (pintype "passive"))
      (node (ref "U5") (pin "1") (pinfunction "OUT_1") (pintype "passive"))
      (node (ref "X2") (pin "1") (pinfunction "1_1") (pintype "passive"))
      (node (ref "X3") (pin "1") (pinfunction "1_1") (pintype "passive"))
    )
    (net (code "63") (name "5V") (class "Default")
      (node (ref "C12") (pin "1") (pinfunction "1_1") (pintype "passive"))
      (node (ref "C13") (pin "1") (pinfunction "1_1") (pintype "passive"))
      (node (ref "C14") (pin "1") (pinfunction "1_1") (pintype "passive"))
      (node (ref "C18") (pin "2") (pinfunction "2_2") (pintype "passive"))
      (node (ref "C26") (pin "2") (pinfunction "2_2") (pintype "passive"))
      (node (ref "C27") (pin "2") (pinfunction "2_2") (pintype "passive"))
      (node (ref "C33") (pin "2") (pinfunction "2_2") (pintype "passive"))
      (node (ref "C4") (pin "1") (pinfunction "1_1") (pintype "passive"))
      (node (ref "D2") (pin "2") (pinfunction "2_2") (pintype "passive"))
      (node (ref "D4") (pin "5") (pinfunction "VBUS_5") (pintype "passive"))
      (node (ref "L1") (pin "2") (pinfunction "2_2") (pintype "passive"))
      (node (ref "R13") (pin "1") (pinfunction "1_1") (pintype "passive"))
      (node (ref "R138") (pin "1") (pinfunction "1_1") (pintype "passive"))
      (node (ref "R2") (pin "2") (pinfunction "2_2") (pintype "passive"))
      (node (ref "U2") (pin "1") (pinfunction "IN_1") (pintype "passive"))
      (node (ref "U4") (pin "3") (pinfunction "VCC_3") (pintype "passive"))
      (node (ref "U5") (pin "6") (pinfunction "IN_6") (pintype "passive"))
      (node (ref "X4") (pin "1") (pinfunction "1_1") (pintype "passive"))
    )
    (net (code "64") (name "GND") (class "Default")
      (node (ref "C1") (pin "1") (pinfunction "1_1") (pintype "passive"))
      (node (ref "C10") (pin "2") (pinfunction "2_2") (pintype "passive"))
      (node (ref "C11") (pin "2") (pinfunction "2_2") (pintype "passive"))
      (node (ref "C12") (pin "2") (pinfunction "2_2") (pintype "passive"))
      (node (ref "C13") (pin "2") (pinfunction "2_2") (pintype "passive"))
      (node (ref "C14") (pin "2") (pinfunction "2_2") (pintype "passive"))
      (node (ref "C15") (pin "2") (pinfunction "2_2") (pintype "passive"))
      (node (ref "C16") (pin "1") (pinfunction "1_1") (pintype "passive"))
      (node (ref "C17") (pin "2") (pinfunction "2_2") (pintype "passive"))
      (node (ref "C18") (pin "1") (pinfunction "1_1") (pintype "passive"))
      (node (ref "C19") (pin "2") (pinfunction "2_2") (pintype "passive"))
      (node (ref "C2") (pin "2") (pinfunction "2_2") (pintype "passive"))
      (node (ref "C20") (pin "1") (pinfunction "1_1") (pintype "passive"))
      (node (ref "C23") (pin "2") (pinfunction "2_2") (pintype "passive"))
      (node (ref "C25") (pin "1") (pinfunction "1_1") (pintype "passive"))
      (node (ref "C26") (pin "1") (pinfunction "1_1") (pintype "passive"))
      (node (ref "C27") (pin "1") (pinfunction "1_1") (pintype "passive"))
      (node (ref "C28") (pin "1") (pinfunction "1_1") (pintype "passive"))
      (node (ref "C3") (pin "2") (pinfunction "2_2") (pintype "passive"))
      (node (ref "C33") (pin "1") (pinfunction "1_1") (pintype "passive"))
      (node (ref "C34") (pin "1") (pinfunction "1_1") (pintype "passive"))
      (node (ref "C35") (pin "2") (pinfunction "2_2") (pintype "passive"))
      (node (ref "C36") (pin "1") (pinfunction "1_1") (pintype "passive"))
      (node (ref "C37") (pin "1") (pinfunction "1_1") (pintype "passive"))
      (node (ref "C38") (pin "1") (pinfunction "1_1") (pintype "passive"))
      (node (ref "C39") (pin "1") (pinfunction "1_1") (pintype "passive"))
      (node (ref "C4") (pin "2") (pinfunction "2_2") (pintype "passive"))
      (node (ref "C5") (pin "2") (pinfunction "2_2") (pintype "passive"))
      (node (ref "C6") (pin "2") (pinfunction "2_2") (pintype "passive"))
      (node (ref "C7") (pin "2") (pinfunction "2_2") (pintype "passive"))
      (node (ref "C71") (pin "1") (pinfunction "1_1") (pintype "passive"))
      (node (ref "C72") (pin "1") (pinfunction "1_1") (pintype "passive"))
      (node (ref "C8") (pin "2") (pinfunction "2_2") (pintype "passive"))
      (node (ref "C9") (pin "2") (pinfunction "2_2") (pintype "passive"))
      (node (ref "CN2") (pin "5") (pinfunction "5_5") (pintype "passive"))
      (node (ref "CN2") (pin "7") (pinfunction "7_7") (pintype "passive"))
      (node (ref "CN2") (pin "8") (pinfunction "8_8") (pintype "passive"))
      (node (ref "CN3") (pin "3") (pinfunction "3_3") (pintype "passive"))
      (node (ref "CN3") (pin "4") (pinfunction "4_4") (pintype "passive"))
      (node (ref "D1") (pin "1") (pinfunction "A_1") (pintype "passive"))
      (node (ref "D4") (pin "2") (pinfunction "GND_2") (pintype "passive"))
      (node (ref "LED1") (pin "2") (pinfunction "A_2") (pintype "passive"))
      (node (ref "LED2") (pin "2") (pinfunction "A_2") (pintype "passive"))
      (node (ref "LED3") (pin "2") (pinfunction "A_2") (pintype "passive"))
      (node (ref "R12") (pin "1") (pinfunction "1_1") (pintype "passive"))
      (node (ref "R14") (pin "2") (pinfunction "2_2") (pintype "passive"))
      (node (ref "R25") (pin "1") (pinfunction "1_1") (pintype "passive"))
      (node (ref "R26") (pin "1") (pinfunction "1_1") (pintype "passive"))
      (node (ref "R4") (pin "1") (pinfunction "1_1") (pintype "passive"))
      (node (ref "R9") (pin "1") (pinfunction "1_1") (pintype "passive"))
      (node (ref "SW1") (pin "1") (pinfunction "1_1") (pintype "passive"))
      (node (ref "SW1") (pin "4") (pinfunction "4_4") (pintype "passive"))
      (node (ref "SW2") (pin "1") (pinfunction "1_1") (pintype "passive"))
      (node (ref "SW2") (pin "4") (pinfunction "4_4") (pintype "passive"))
      (node (ref "SW3") (pin "1") (pinfunction "1_1") (pintype "passive"))
      (node (ref "SW3") (pin "4") (pinfunction "4_4") (pintype "passive"))
      (node (ref "SW4") (pin "1") (pinfunction "1_1") (pintype "passive"))
      (node (ref "SW4") (pin "4") (pinfunction "4_4") (pintype "passive"))
      (node (ref "SW5") (pin "1") (pinfunction "1_1") (pintype "passive"))
      (node (ref "SW5") (pin "4") (pinfunction "4_4") (pintype "passive"))
      (node (ref "U1") (pin "15") (pinfunction "VSS_15") (pintype "passive"))
      (node (ref "U1") (pin "27") (pinfunction "VSSA_27") (pintype "passive"))
      (node (ref "U1") (pin "31") (pinfunction "VSS_31") (pintype "passive"))
      (node (ref "U1") (pin "47") (pinfunction "VSS_47") (pintype "passive"))
      (node (ref "U1") (pin "63") (pinfunction "VSS_63") (pintype "passive"))
      (node (ref "U2") (pin "3") (pinfunction "GND_3") (pintype "passive"))
      (node (ref "U3") (pin "2") (pinfunction "A_2") (pintype "passive"))
      (node (ref "U4") (pin "2") (pinfunction "GND_2") (pintype "passive"))
      (node (ref "U4") (pin "8") (pinfunction "S_8") (pintype "passive"))
      (node (ref "U5") (pin "2") (pinfunction "NC_2") (pintype "passive"))
      (node (ref "U5") (pin "5") (pinfunction "GND_5") (pintype "passive"))
      (node (ref "U5") (pin "7") (pinfunction "EP_7") (pintype "passive"))
      (node (ref "U6") (pin "27") (pinfunction "DGND_27") (pintype "passive"))
      (node (ref "U6") (pin "35") (pinfunction "AGND_35") (pintype "passive"))
      (node (ref "U6") (pin "43") (pinfunction "BGND_43") (pintype "passive"))
      (node (ref "U6") (pin "49") (pinfunction "EP_49") (pintype "passive"))
      (node (ref "USB1") (pin "1") (pinfunction "SHELL_1") (pintype "passive"))
      (node (ref "USB1") (pin "2") (pinfunction "SHELL_2") (pintype "passive"))
      (node (ref "USB1") (pin "3") (pinfunction "SHELL_3") (pintype "passive"))
      (node (ref "USB1") (pin "4") (pinfunction "SHELL_4") (pintype "passive"))
      (node (ref "USB1") (pin "A1B12") (pinfunction "GND_A1B12") (pintype "passive"))
      (node (ref "USB1") (pin "B1A12") (pinfunction "GND_B1A12") (pintype "passive"))
      (node (ref "X1") (pin "2") (pinfunction "GND_2") (pintype "passive"))
      (node (ref "X1") (pin "4") (pinfunction "GND_4") (pintype "passive"))
      (node (ref "X2") (pin "2") (pinfunction "2_2") (pintype "passive"))
      (node (ref "X2") (pin "5") (pinfunction "5_5") (pintype "passive"))
      (node (ref "X2") (pin "6") (pinfunction "6_6") (pintype "passive"))
      (node (ref "X3") (pin "2") (pinfunction "2_2") (pintype "passive"))
      (node (ref "X3") (pin "5") (pinfunction "5_5") (pintype "passive"))
      (node (ref "X3") (pin "6") (pinfunction "6_6") (pintype "passive"))
      (node (ref "X4") (pin "2") (pinfunction "2_2") (pintype "passive"))
      (node (ref "X4") (pin "5") (pinfunction "5_5") (pintype "passive"))
      (node (ref "X4") (pin "6") (pinfunction "6_6") (pintype "passive"))
    )
    (net (code "65") (name "Net-(C5-Pad1)") (class "Default")
      (node (ref "C5") (pin "1") (pinfunction "1_1") (pintype "passive"))
      (node (ref "R7") (pin "1") (pinfunction "1_1") (pintype "passive"))
      (node (ref "R8") (pin "2") (pinfunction "2_2") (pintype "passive"))
      (node (ref "R9") (pin "2") (pinfunction "2_2") (pintype "passive"))
    )
    (net (code "66") (name "Net-(LED1-K)") (class "Default")
      (node (ref "LED1") (pin "1") (pinfunction "K_1") (pintype "passive"))
      (node (ref "R1") (pin "1") (pinfunction "1_1") (pintype "passive"))
    )
    (net (code "67") (name "Net-(LED2-K)") (class "Default")
      (node (ref "LED2") (pin "1") (pinfunction "K_1") (pintype "passive"))
      (node (ref "R2") (pin "1") (pinfunction "1_1") (pintype "passive"))
    )
    (net (code "68") (name "Net-(R39-Pad1)") (class "Default")
      (node (ref "R39") (pin "1") (pinfunction "1_1") (pintype "passive"))
      (node (ref "X4") (pin "4") (pinfunction "4_4") (pintype "passive"))
    )
    (net (code "69") (name "Net-(R40-Pad1)") (class "Default")
      (node (ref "R40") (pin "1") (pinfunction "1_1") (pintype "passive"))
      (node (ref "X4") (pin "3") (pinfunction "3_3") (pintype "passive"))
    )
    (net (code "70") (name "Net-(U1-VDDA)") (class "Default")
      (node (ref "C19") (pin "1") (pinfunction "1_1") (pintype "passive"))
      (node (ref "L3") (pin "2") (pinfunction "2_2") (pintype "passive"))
      (node (ref "U1") (pin "29") (pinfunction "VDDA_29") (pintype "passive"))
    )
    (net (code "71") (name "Net-(U1-VREF+)") (class "Default")
      (node (ref "C16") (pin "2") (pinfunction "2_2") (pintype "passive"))
      (node (ref "L2") (pin "2") (pinfunction "2_2") (pintype "passive"))
      (node (ref "U1") (pin "28") (pinfunction "VREF+_28") (pintype "passive"))
    )
    (net (code "72") (name "Net-(U3-K)") (class "Default")
      (node (ref "C21") (pin "2") (pinfunction "2_2") (pintype "passive"))
      (node (ref "L1") (pin "1") (pinfunction "1_1") (pintype "passive"))
      (node (ref "U3") (pin "1") (pinfunction "K_1") (pintype "passive"))
      (node (ref "U6") (pin "45") (pinfunction "SW_45") (pintype "passive"))
    )
    (net (code "73") (name "Net-(U5-EN)") (class "Default")
      (node (ref "R138") (pin "2") (pinfunction "2_2") (pintype "passive"))
      (node (ref "U5") (pin "4") (pinfunction "EN_4") (pintype "passive"))
    )
    (net (code "74") (name "Net-(U6-CB)") (class "Default")
      (node (ref "C21") (pin "1") (pinfunction "1_1") (pintype "passive"))
      (node (ref "U6") (pin "44") (pinfunction "CB_44") (pintype "passive"))
    )
    (net (code "75") (name "Net-(U6-CPH)") (class "Default")
      (node (ref "C22") (pin "1") (pinfunction "1_1") (pintype "passive"))
      (node (ref "U6") (pin "4") (pinfunction "CPH_4") (pintype "passive"))
    )
    (net (code "76") (name "Net-(U6-CPL)") (class "Default")
      (node (ref "C22") (pin "2") (pinfunction "2_2") (pintype "passive"))
      (node (ref "U6") (pin "3") (pinfunction "CPL_3") (pintype "passive"))
    )
    (net (code "77") (name "Net-(U6-DVDD)") (class "Default")
      (node (ref "C23") (pin "1") (pinfunction "1_1") (pintype "passive"))
      (node (ref "U6") (pin "36") (pinfunction "DVDD_36") (pintype "passive"))
    )
    (net (code "78") (name "Net-(U6-FB)") (class "Default")
      (node (ref "R12") (pin "2") (pinfunction "2_2") (pintype "passive"))
      (node (ref "R13") (pin "2") (pinfunction "2_2") (pintype "passive"))
      (node (ref "U6") (pin "1") (pinfunction "FB_1") (pintype "passive"))
    )
    (net (code "79") (name "Net-(U6-SOA)") (class "Default")
      (node (ref "R21") (pin "2") (pinfunction "2_2") (pintype "passive"))
      (node (ref "U6") (pin "25") (pinfunction "SOA_25") (pintype "passive"))
    )
    (net (code "80") (name "Net-(U6-SOB)") (class "Default")
      (node (ref "R20") (pin "2") (pinfunction "2_2") (pintype "passive"))
      (node (ref "U6") (pin "24") (pinfunction "SOB_24") (pintype "passive"))
    )
    (net (code "81") (name "Net-(U6-SOC)") (class "Default")
      (node (ref "R19") (pin "2") (pinfunction "2_2") (pintype "passive"))
      (node (ref "U6") (pin "23") (pinfunction "SOC_23") (pintype "passive"))
    )
    (net (code "82") (name "Net-(U6-VCP)") (class "Default")
      (node (ref "C24") (pin "2") (pinfunction "2_2") (pintype "passive"))
      (node (ref "U6") (pin "5") (pinfunction "VCP_5") (pintype "passive"))
    )
    (net (code "83") (name "Net-(U6-nSHDN)") (class "Default")
      (node (ref "R11") (pin "1") (pinfunction "1_1") (pintype "passive"))
      (node (ref "U6") (pin "48") (pinfunction "nSHDN_48") (pintype "passive"))
    )
    (net (code "84") (name "Net-(USB1-CC1)") (class "Default")
      (node (ref "R26") (pin "2") (pinfunction "2_2") (pintype "passive"))
      (node (ref "USB1") (pin "A5") (pinfunction "CC1_A5") (pintype "passive"))
    )
    (net (code "85") (name "Net-(USB1-CC2)") (class "Default")
      (node (ref "R25") (pin "2") (pinfunction "2_2") (pintype "passive"))
      (node (ref "USB1") (pin "B5") (pinfunction "CC2_B5") (pintype "passive"))
    )
    (net (code "86") (name "PGND") (class "Default")
      (node (ref "C29") (pin "2") (pinfunction "2_2") (pintype "passive"))
      (node (ref "C30") (pin "1") (pinfunction "1_1") (pintype "passive"))
      (node (ref "C31") (pin "1") (pinfunction "1_1") (pintype "passive"))
      (node (ref "C32") (pin "1") (pinfunction "1_1") (pintype "passive"))
      (node (ref "CN1") (pin "2") (pinfunction "2_2") (pintype "passive"))
      (node (ref "D3") (pin "2") (pinfunction "A_2") (pintype "passive"))
      (node (ref "R14") (pin "1") (pinfunction "1_1") (pintype "passive"))
      (node (ref "R22") (pin "1") (pinfunction "1_1") (pintype "passive"))
      (node (ref "R23") (pin "1") (pinfunction "1_1") (pintype "passive"))
      (node (ref "R24") (pin "1") (pinfunction "1_1") (pintype "passive"))
      (node (ref "R35") (pin "1") (pinfunction "1_1") (pintype "passive"))
      (node (ref "R36") (pin "1") (pinfunction "1_1") (pintype "passive"))
      (node (ref "R37") (pin "1") (pinfunction "1_1") (pintype "passive"))
      (node (ref "R41") (pin "1") (pinfunction "1_1") (pintype "passive"))
      (node (ref "U6") (pin "12") (pinfunction "SNA_12") (pintype "passive"))
      (node (ref "U6") (pin "13") (pinfunction "SNB_13") (pintype "passive"))
      (node (ref "U6") (pin "2") (pinfunction "PGND_2") (pintype "passive"))
      (node (ref "U6") (pin "22") (pinfunction "SNC_22") (pintype "passive"))
    )
    (net (code "87") (name "VREF") (class "Default")
      (node (ref "C3") (pin "1") (pinfunction "1_1") (pintype "passive"))
      (node (ref "C35") (pin "1") (pinfunction "1_1") (pintype "passive"))
      (node (ref "L2") (pin "1") (pinfunction "1_1") (pintype "passive"))
      (node (ref "L3") (pin "1") (pinfunction "1_1") (pintype "passive"))
      (node (ref "U2") (pin "2") (pinfunction "OUT_2") (pintype "passive"))
      (node (ref "U6") (pin "26") (pinfunction "VREF_26") (pintype "passive"))
    )
    (net (code "88") (name "unconnected-(U1-PB2-Pad26)") (class "Default")
      (node (ref "U1") (pin "26") (pinfunction "PB2_26") (pintype "passive+no_connect"))
    )
    (net (code "89") (name "unconnected-(U1-PB10-Pad30)") (class "Default")
      (node (ref "U1") (pin "30") (pinfunction "PB10_30") (pintype "passive+no_connect"))
    )
    (net (code "90") (name "unconnected-(U1-PC2-Pad10)") (class "Default")
      (node (ref "U1") (pin "10") (pinfunction "PC2_10") (pintype "passive+no_connect"))
    )
    (net (code "91") (name "unconnected-(U1-PC3-Pad11)") (class "Default")
      (node (ref "U1") (pin "11") (pinfunction "PC3_11") (pintype "passive+no_connect"))
    )
    (net (code "92") (name "unconnected-(U1-PC7-Pad39)") (class "Default")
      (node (ref "U1") (pin "39") (pinfunction "PC7_39") (pintype "passive+no_connect"))
    )
    (net (code "93") (name "unconnected-(U1-PC13-Pad2)") (class "Default")
      (node (ref "U1") (pin "2") (pinfunction "PC13_2") (pintype "passive+no_connect"))
    )
    (net (code "94") (name "unconnected-(U1-PC14-OSC32_IN-Pad3)") (class "Default")
      (node (ref "U1") (pin "3") (pinfunction "PC14-OSC32_IN_3") (pintype "passive+no_connect"))
    )
    (net (code "95") (name "unconnected-(U1-PC15-OSC32_OUT-Pad4)") (class "Default")
      (node (ref "U1") (pin "4") (pinfunction "PC15-OSC32_OUT_4") (pintype "passive+no_connect"))
    )
    (net (code "96") (name "unconnected-(U5-PG-Pad3)") (class "Default")
      (node (ref "U5") (pin "3") (pinfunction "PG_3") (pintype "passive+no_connect"))
    )
    (net (code "97") (name "unconnected-(U6-NC-Pad46)") (class "Default")
      (node (ref "U6") (pin "46") (pinfunction "NC_46") (pintype "passive+no_connect"))
    )
    (net (code "98") (name "unconnected-(USB1-SBU1-PadA8)") (class "Default")
      (node (ref "USB1") (pin "A8") (pinfunction "SBU1_A8") (pintype "passive+no_connect"))
    )
    (net (code "99") (name "unconnected-(USB1-SBU2-PadB8)") (class "Default")
      (node (ref "USB1") (pin "B8") (pinfunction "SBU2_B8") (pintype "passive+no_connect"))
    )
  )
)
